# DSP_GPIO_Part3.net
KiCad netlist of a schematic drawn in Altium Designer
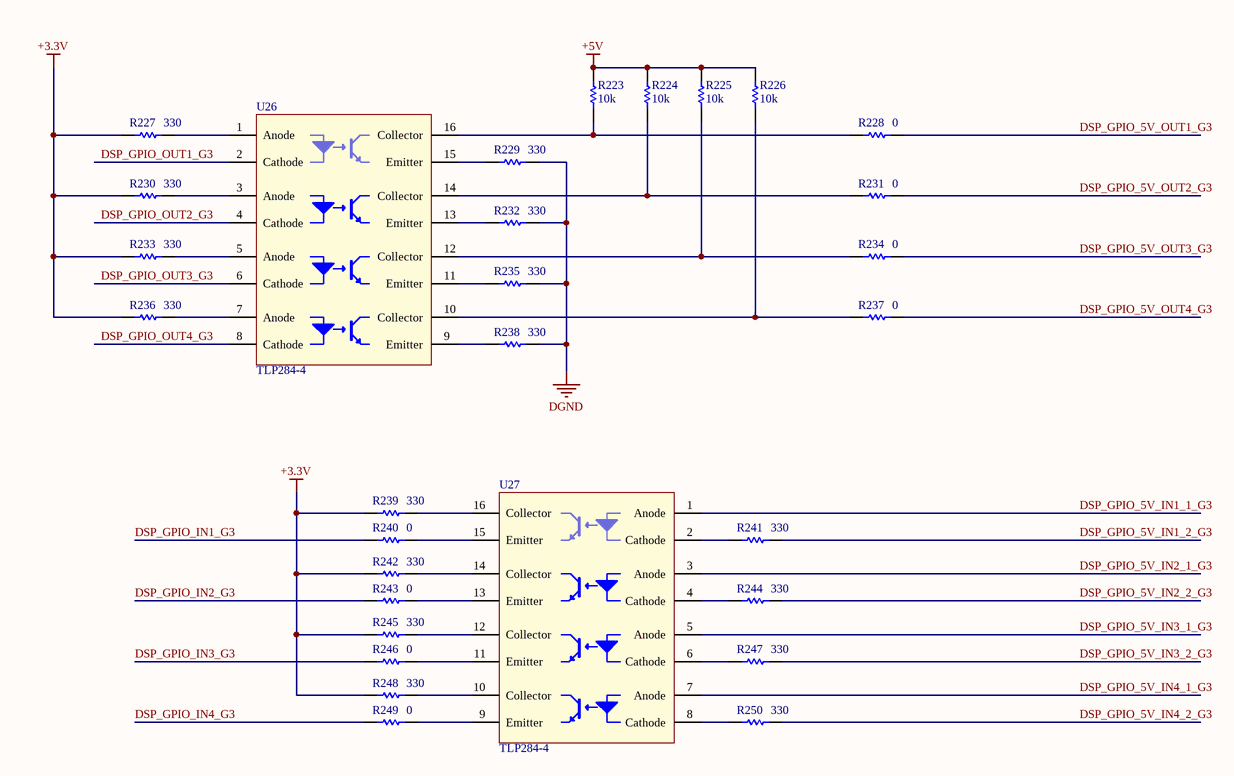
[diagram p0: DSP_GPIO_Part3.SchDoc]

(export (version "E")
  (design (tool "Eeschema 10.0.6"))
  (components
    (comp (ref "R223")
      (value "10k")
      (footprint "1608[0603]")
      (description "Resistor")
      (fields (field (name "Comment") "Res1") (field (name "PUBLISHER") "Altium Limited"))
      (libsource (lib "Miscellaneous Devices") (part "Res1"))
    )
    (comp (ref "R224")
      (value "10k")
      (footprint "1608[0603]")
      (description "Resistor")
      (fields (field (name "Comment") "Res1") (field (name "PUBLISHER") "Altium Limited"))
      (libsource (lib "Miscellaneous Devices") (part "Res1"))
    )
    (comp (ref "R225")
      (value "10k")
      (footprint "1608[0603]")
      (description "Resistor")
      (fields (field (name "Comment") "Res1") (field (name "PUBLISHER") "Altium Limited"))
      (libsource (lib "Miscellaneous Devices") (part "Res1"))
    )
    (comp (ref "R226")
      (value "10k")
      (footprint "1608[0603]")
      (description "Resistor")
      (fields (field (name "Comment") "Res1") (field (name "PUBLISHER") "Altium Limited"))
      (libsource (lib "Miscellaneous Devices") (part "Res1"))
    )
    (comp (ref "R227")
      (value "330")
      (footprint "1608[0603]")
      (description "Resistor")
      (fields (field (name "Comment") "Res1") (field (name "PUBLISHER") "Altium Limited"))
      (libsource (lib "Miscellaneous Devices") (part "Res1"))
    )
    (comp (ref "R228")
      (value "0")
      (footprint "1608[0603]")
      (description "Resistor")
      (fields (field (name "Comment") "Res1") (field (name "PUBLISHER") "Altium Limited"))
      (libsource (lib "Miscellaneous Devices") (part "Res1"))
    )
    (comp (ref "R229")
      (value "330")
      (footprint "1608[0603]")
      (description "Resistor")
      (fields (field (name "Comment") "Res1") (field (name "PUBLISHER") "Altium Limited"))
      (libsource (lib "Miscellaneous Devices") (part "Res1"))
    )
    (comp (ref "R230")
      (value "330")
      (footprint "1608[0603]")
      (description "Resistor")
      (fields (field (name "Comment") "Res1") (field (name "PUBLISHER") "Altium Limited"))
      (libsource (lib "Miscellaneous Devices") (part "Res1"))
    )
    (comp (ref "R231")
      (value "0")
      (footprint "1608[0603]")
      (description "Resistor")
      (fields (field (name "Comment") "Res1") (field (name "PUBLISHER") "Altium Limited"))
      (libsource (lib "Miscellaneous Devices") (part "Res1"))
    )
    (comp (ref "R232")
      (value "330")
      (footprint "1608[0603]")
      (description "Resistor")
      (fields (field (name "Comment") "Res1") (field (name "PUBLISHER") "Altium Limited"))
      (libsource (lib "Miscellaneous Devices") (part "Res1"))
    )
    (comp (ref "R233")
      (value "330")
      (footprint "1608[0603]")
      (description "Resistor")
      (fields (field (name "Comment") "Res1") (field (name "PUBLISHER") "Altium Limited"))
      (libsource (lib "Miscellaneous Devices") (part "Res1"))
    )
    (comp (ref "R234")
      (value "0")
      (footprint "1608[0603]")
      (description "Resistor")
      (fields (field (name "Comment") "Res1") (field (name "PUBLISHER") "Altium Limited"))
      (libsource (lib "Miscellaneous Devices") (part "Res1"))
    )
    (comp (ref "R235")
      (value "330")
      (footprint "1608[0603]")
      (description "Resistor")
      (fields (field (name "Comment") "Res1") (field (name "PUBLISHER") "Altium Limited"))
      (libsource (lib "Miscellaneous Devices") (part "Res1"))
    )
    (comp (ref "R236")
      (value "330")
      (footprint "1608[0603]")
      (description "Resistor")
      (fields (field (name "Comment") "Res1") (field (name "PUBLISHER") "Altium Limited"))
      (libsource (lib "Miscellaneous Devices") (part "Res1"))
    )
    (comp (ref "R237")
      (value "0")
      (footprint "1608[0603]")
      (description "Resistor")
      (fields (field (name "Comment") "Res1") (field (name "PUBLISHER") "Altium Limited"))
      (libsource (lib "Miscellaneous Devices") (part "Res1"))
    )
    (comp (ref "R238")
      (value "330")
      (footprint "1608[0603]")
      (description "Resistor")
      (fields (field (name "Comment") "Res1") (field (name "PUBLISHER") "Altium Limited"))
      (libsource (lib "Miscellaneous Devices") (part "Res1"))
    )
    (comp (ref "R239")
      (value "330")
      (footprint "1608[0603]")
      (description "Resistor")
      (fields (field (name "Comment") "Res1") (field (name "PUBLISHER") "Altium Limited"))
      (libsource (lib "Miscellaneous Devices") (part "Res1"))
    )
    (comp (ref "R240")
      (value "0")
      (footprint "1608[0603]")
      (description "Resistor")
      (fields (field (name "Comment") "Res1") (field (name "PUBLISHER") "Altium Limited"))
      (libsource (lib "Miscellaneous Devices") (part "Res1"))
    )
    (comp (ref "R241")
      (value "330")
      (footprint "1608[0603]")
      (description "Resistor")
      (fields (field (name "Comment") "Res1") (field (name "PUBLISHER") "Altium Limited"))
      (libsource (lib "Miscellaneous Devices") (part "Res1"))
    )
    (comp (ref "R242")
      (value "330")
      (footprint "1608[0603]")
      (description "Resistor")
      (fields (field (name "Comment") "Res1") (field (name "PUBLISHER") "Altium Limited"))
      (libsource (lib "Miscellaneous Devices") (part "Res1"))
    )
    (comp (ref "R243")
      (value "0")
      (footprint "1608[0603]")
      (description "Resistor")
      (fields (field (name "Comment") "Res1") (field (name "PUBLISHER") "Altium Limited"))
      (libsource (lib "Miscellaneous Devices") (part "Res1"))
    )
    (comp (ref "R244")
      (value "330")
      (footprint "1608[0603]")
      (description "Resistor")
      (fields (field (name "Comment") "Res1") (field (name "PUBLISHER") "Altium Limited"))
      (libsource (lib "Miscellaneous Devices") (part "Res1"))
    )
    (comp (ref "R245")
      (value "330")
      (footprint "1608[0603]")
      (description "Resistor")
      (fields (field (name "Comment") "Res1") (field (name "PUBLISHER") "Altium Limited"))
      (libsource (lib "Miscellaneous Devices") (part "Res1"))
    )
    (comp (ref "R246")
      (value "0")
      (footprint "1608[0603]")
      (description "Resistor")
      (fields (field (name "Comment") "Res1") (field (name "PUBLISHER") "Altium Limited"))
      (libsource (lib "Miscellaneous Devices") (part "Res1"))
    )
    (comp (ref "R247")
      (value "330")
      (footprint "1608[0603]")
      (description "Resistor")
      (fields (field (name "Comment") "Res1") (field (name "PUBLISHER") "Altium Limited"))
      (libsource (lib "Miscellaneous Devices") (part "Res1"))
    )
    (comp (ref "R248")
      (value "330")
      (footprint "1608[0603]")
      (description "Resistor")
      (fields (field (name "Comment") "Res1") (field (name "PUBLISHER") "Altium Limited"))
      (libsource (lib "Miscellaneous Devices") (part "Res1"))
    )
    (comp (ref "R249")
      (value "0")
      (footprint "1608[0603]")
      (description "Resistor")
      (fields (field (name "Comment") "Res1") (field (name "PUBLISHER") "Altium Limited"))
      (libsource (lib "Miscellaneous Devices") (part "Res1"))
    )
    (comp (ref "R250")
      (value "330")
      (footprint "1608[0603]")
      (description "Resistor")
      (fields (field (name "Comment") "Res1") (field (name "PUBLISHER") "Altium Limited"))
      (libsource (lib "Miscellaneous Devices") (part "Res1"))
    )
    (comp (ref "U26")
      (value "TLP284-4")
      (footprint "TLP284-4")
      (libsource (lib "DSP_FPGA_Lib") (part "TLP284-4"))
    )
    (comp (ref "U27")
      (value "TLP284-4")
      (footprint "TLP284-4")
      (libsource (lib "DSP_FPGA_Lib") (part "TLP284-4"))
    )
  )
  (nets
    (net (code "1") (name "+3.3V") (class "Default")
      (node (ref "R227") (pin "1") (pinfunction "1_1") (pintype "passive"))
      (node (ref "R230") (pin "1") (pinfunction "1_1") (pintype "passive"))
      (node (ref "R233") (pin "1") (pinfunction "1_1") (pintype "passive"))
      (node (ref "R236") (pin "1") (pinfunction "1_1") (pintype "passive"))
      (node (ref "R239") (pin "1") (pinfunction "1_1") (pintype "passive"))
      (node (ref "R242") (pin "1") (pinfunction "1_1") (pintype "passive"))
      (node (ref "R245") (pin "1") (pinfunction "1_1") (pintype "passive"))
      (node (ref "R248") (pin "1") (pinfunction "1_1") (pintype "passive"))
    )
    (net (code "2") (name "+5V") (class "Default")
      (node (ref "R223") (pin "2") (pinfunction "2_2") (pintype "passive"))
      (node (ref "R224") (pin "2") (pinfunction "2_2") (pintype "passive"))
      (node (ref "R225") (pin "2") (pinfunction "2_2") (pintype "passive"))
      (node (ref "R226") (pin "2") (pinfunction "2_2") (pintype "passive"))
    )
    (net (code "3") (name "/DSP_GPIO_5V_IN1_1_G3") (class "Default")
      (node (ref "U27") (pin "1") (pinfunction "Anode_1") (pintype "passive"))
    )
    (net (code "4") (name "/DSP_GPIO_5V_IN1_2_G3") (class "Default")
      (node (ref "R241") (pin "2") (pinfunction "2_2") (pintype "passive"))
    )
    (net (code "5") (name "/DSP_GPIO_5V_IN2_1_G3") (class "Default")
      (node (ref "U27") (pin "3") (pinfunction "Anode_3") (pintype "passive"))
    )
    (net (code "6") (name "/DSP_GPIO_5V_IN2_2_G3") (class "Default")
      (node (ref "R244") (pin "2") (pinfunction "2_2") (pintype "passive"))
    )
    (net (code "7") (name "/DSP_GPIO_5V_IN3_1_G3") (class "Default")
      (node (ref "U27") (pin "5") (pinfunction "Anode_5") (pintype "passive"))
    )
    (net (code "8") (name "/DSP_GPIO_5V_IN3_2_G3") (class "Default")
      (node (ref "R247") (pin "2") (pinfunction "2_2") (pintype "passive"))
    )
    (net (code "9") (name "/DSP_GPIO_5V_IN4_1_G3") (class "Default")
      (node (ref "U27") (pin "7") (pinfunction "Anode_7") (pintype "passive"))
    )
    (net (code "10") (name "/DSP_GPIO_5V_IN4_2_G3") (class "Default")
      (node (ref "R250") (pin "2") (pinfunction "2_2") (pintype "passive"))
    )
    (net (code "11") (name "/DSP_GPIO_5V_OUT1_G3") (class "Default")
      (node (ref "R228") (pin "2") (pinfunction "2_2") (pintype "passive"))
    )
    (net (code "12") (name "/DSP_GPIO_5V_OUT2_G3") (class "Default")
      (node (ref "R231") (pin "2") (pinfunction "2_2") (pintype "passive"))
    )
    (net (code "13") (name "/DSP_GPIO_5V_OUT3_G3") (class "Default")
      (node (ref "R234") (pin "2") (pinfunction "2_2") (pintype "passive"))
    )
    (net (code "14") (name "/DSP_GPIO_5V_OUT4_G3") (class "Default")
      (node (ref "R237") (pin "2") (pinfunction "2_2") (pintype "passive"))
    )
    (net (code "15") (name "/DSP_GPIO_IN1_G3") (class "Default")
      (node (ref "R240") (pin "1") (pinfunction "1_1") (pintype "passive"))
    )
    (net (code "16") (name "/DSP_GPIO_IN2_G3") (class "Default")
      (node (ref "R243") (pin "1") (pinfunction "1_1") (pintype "passive"))
    )
    (net (code "17") (name "/DSP_GPIO_IN3_G3") (class "Default")
      (node (ref "R246") (pin "1") (pinfunction "1_1") (pintype "passive"))
    )
    (net (code "18") (name "/DSP_GPIO_IN4_G3") (class "Default")
      (node (ref "R249") (pin "1") (pinfunction "1_1") (pintype "passive"))
    )
    (net (code "19") (name "/DSP_GPIO_OUT1_G3") (class "Default")
      (node (ref "U26") (pin "2") (pinfunction "Cathode_2") (pintype "passive"))
    )
    (net (code "20") (name "/DSP_GPIO_OUT2_G3") (class "Default")
      (node (ref "U26") (pin "4") (pinfunction "Cathode_4") (pintype "passive"))
    )
    (net (code "21") (name "/DSP_GPIO_OUT3_G3") (class "Default")
      (node (ref "U26") (pin "6") (pinfunction "Cathode_6") (pintype "passive"))
    )
    (net (code "22") (name "/DSP_GPIO_OUT4_G3") (class "Default")
      (node (ref "U26") (pin "8") (pinfunction "Cathode_8") (pintype "passive"))
    )
    (net (code "23") (name "DGND") (class "Default")
      (node (ref "R229") (pin "2") (pinfunction "2_2") (pintype "passive"))
      (node (ref "R232") (pin "2") (pinfunction "2_2") (pintype "passive"))
      (node (ref "R235") (pin "2") (pinfunction "2_2") (pintype "passive"))
      (node (ref "R238") (pin "2") (pinfunction "2_2") (pintype "passive"))
    )
    (net (code "24") (name "Net-(R223-Pad1)") (class "Default")
      (node (ref "R223") (pin "1") (pinfunction "1_1") (pintype "passive"))
      (node (ref "R228") (pin "1") (pinfunction "1_1") (pintype "passive"))
      (node (ref "U26") (pin "16") (pinfunction "Collector_16") (pintype "passive"))
    )
    (net (code "25") (name "Net-(R224-Pad1)") (class "Default")
      (node (ref "R224") (pin "1") (pinfunction "1_1") (pintype "passive"))
      (node (ref "R231") (pin "1") (pinfunction "1_1") (pintype "passive"))
      (node (ref "U26") (pin "14") (pinfunction "Collector_14") (pintype "passive"))
    )
    (net (code "26") (name "Net-(R225-Pad1)") (class "Default")
      (node (ref "R225") (pin "1") (pinfunction "1_1") (pintype "passive"))
      (node (ref "R234") (pin "1") (pinfunction "1_1") (pintype "passive"))
      (node (ref "U26") (pin "12") (pinfunction "Collector_12") (pintype "passive"))
    )
    (net (code "27") (name "Net-(R226-Pad1)") (class "Default")
      (node (ref "R226") (pin "1") (pinfunction "1_1") (pintype "passive"))
      (node (ref "R237") (pin "1") (pinfunction "1_1") (pintype "passive"))
      (node (ref "U26") (pin "10") (pinfunction "Collector_10") (pintype "passive"))
    )
    (net (code "28") (name "Net-(R227-Pad2)") (class "Default")
      (node (ref "R227") (pin "2") (pinfunction "2_2") (pintype "passive"))
      (node (ref "U26") (pin "1") (pinfunction "Anode_1") (pintype "passive"))
    )
    (net (code "29") (name "Net-(R229-Pad1)") (class "Default")
      (node (ref "R229") (pin "1") (pinfunction "1_1") (pintype "passive"))
      (node (ref "U26") (pin "15") (pinfunction "Emitter_15") (pintype "passive"))
    )
    (net (code "30") (name "Net-(R230-Pad2)") (class "Default")
      (node (ref "R230") (pin "2") (pinfunction "2_2") (pintype "passive"))
      (node (ref "U26") (pin "3") (pinfunction "Anode_3") (pintype "passive"))
    )
    (net (code "31") (name "Net-(R232-Pad1)") (class "Default")
      (node (ref "R232") (pin "1") (pinfunction "1_1") (pintype "passive"))
      (node (ref "U26") (pin "13") (pinfunction "Emitter_13") (pintype "passive"))
    )
    (net (code "32") (name "Net-(R233-Pad2)") (class "Default")
      (node (ref "R233") (pin "2") (pinfunction "2_2") (pintype "passive"))
      (node (ref "U26") (pin "5") (pinfunction "Anode_5") (pintype "passive"))
    )
    (net (code "33") (name "Net-(R235-Pad1)") (class "Default")
      (node (ref "R235") (pin "1") (pinfunction "1_1") (pintype "passive"))
      (node (ref "U26") (pin "11") (pinfunction "Emitter_11") (pintype "passive"))
    )
    (net (code "34") (name "Net-(R236-Pad2)") (class "Default")
      (node (ref "R236") (pin "2") (pinfunction "2_2") (pintype "passive"))
      (node (ref "U26") (pin "7") (pinfunction "Anode_7") (pintype "passive"))
    )
    (net (code "35") (name "Net-(R238-Pad1)") (class "Default")
      (node (ref "R238") (pin "1") (pinfunction "1_1") (pintype "passive"))
      (node (ref "U26") (pin "9") (pinfunction "Emitter_9") (pintype "passive"))
    )
    (net (code "36") (name "Net-(R239-Pad2)") (class "Default")
      (node (ref "R239") (pin "2") (pinfunction "2_2") (pintype "passive"))
      (node (ref "U27") (pin "16") (pinfunction "Collector_16") (pintype "passive"))
    )
    (net (code "37") (name "Net-(R240-Pad2)") (class "Default")
      (node (ref "R240") (pin "2") (pinfunction "2_2") (pintype "passive"))
      (node (ref "U27") (pin "15") (pinfunction "Emitter_15") (pintype "passive"))
    )
    (net (code "38") (name "Net-(R241-Pad1)") (class "Default")
      (node (ref "R241") (pin "1") (pinfunction "1_1") (pintype "passive"))
      (node (ref "U27") (pin "2") (pinfunction "Cathode_2") (pintype "passive"))
    )
    (net (code "39") (name "Net-(R242-Pad2)") (class "Default")
      (node (ref "R242") (pin "2") (pinfunction "2_2") (pintype "passive"))
      (node (ref "U27") (pin "14") (pinfunction "Collector_14") (pintype "passive"))
    )
    (net (code "40") (name "Net-(R243-Pad2)") (class "Default")
      (node (ref "R243") (pin "2") (pinfunction "2_2") (pintype "passive"))
      (node (ref "U27") (pin "13") (pinfunction "Emitter_13") (pintype "passive"))
    )
    (net (code "41") (name "Net-(R244-Pad1)") (class "Default")
      (node (ref "R244") (pin "1") (pinfunction "1_1") (pintype "passive"))
      (node (ref "U27") (pin "4") (pinfunction "Cathode_4") (pintype "passive"))
    )
    (net (code "42") (name "Net-(R245-Pad2)") (class "Default")
      (node (ref "R245") (pin "2") (pinfunction "2_2") (pintype "passive"))
      (node (ref "U27") (pin "12") (pinfunction "Collector_12") (pintype "passive"))
    )
    (net (code "43") (name "Net-(R246-Pad2)") (class "Default")
      (node (ref "R246") (pin "2") (pinfunction "2_2") (pintype "passive"))
      (node (ref "U27") (pin "11") (pinfunction "Emitter_11") (pintype "passive"))
    )
    (net (code "44") (name "Net-(R247-Pad1)") (class "Default")
      (node (ref "R247") (pin "1") (pinfunction "1_1") (pintype "passive"))
      (node (ref "U27") (pin "6") (pinfunction "Cathode_6") (pintype "passive"))
    )
    (net (code "45") (name "Net-(R248-Pad2)") (class "Default")
      (node (ref "R248") (pin "2") (pinfunction "2_2") (pintype "passive"))
      (node (ref "U27") (pin "10") (pinfunction "Collector_10") (pintype "passive"))
    )
    (net (code "46") (name "Net-(R249-Pad2)") (class "Default")
      (node (ref "R249") (pin "2") (pinfunction "2_2") (pintype "passive"))
      (node (ref "U27") (pin "9") (pinfunction "Emitter_9") (pintype "passive"))
    )
    (net (code "47") (name "Net-(R250-Pad1)") (class "Default")
      (node (ref "R250") (pin "1") (pinfunction "1_1") (pintype "passive"))
      (node (ref "U27") (pin "8") (pinfunction "Cathode_8") (pintype "passive"))
    )
  )
)
